# Main.net
KiCad netlist of a schematic drawn in Altium Designer
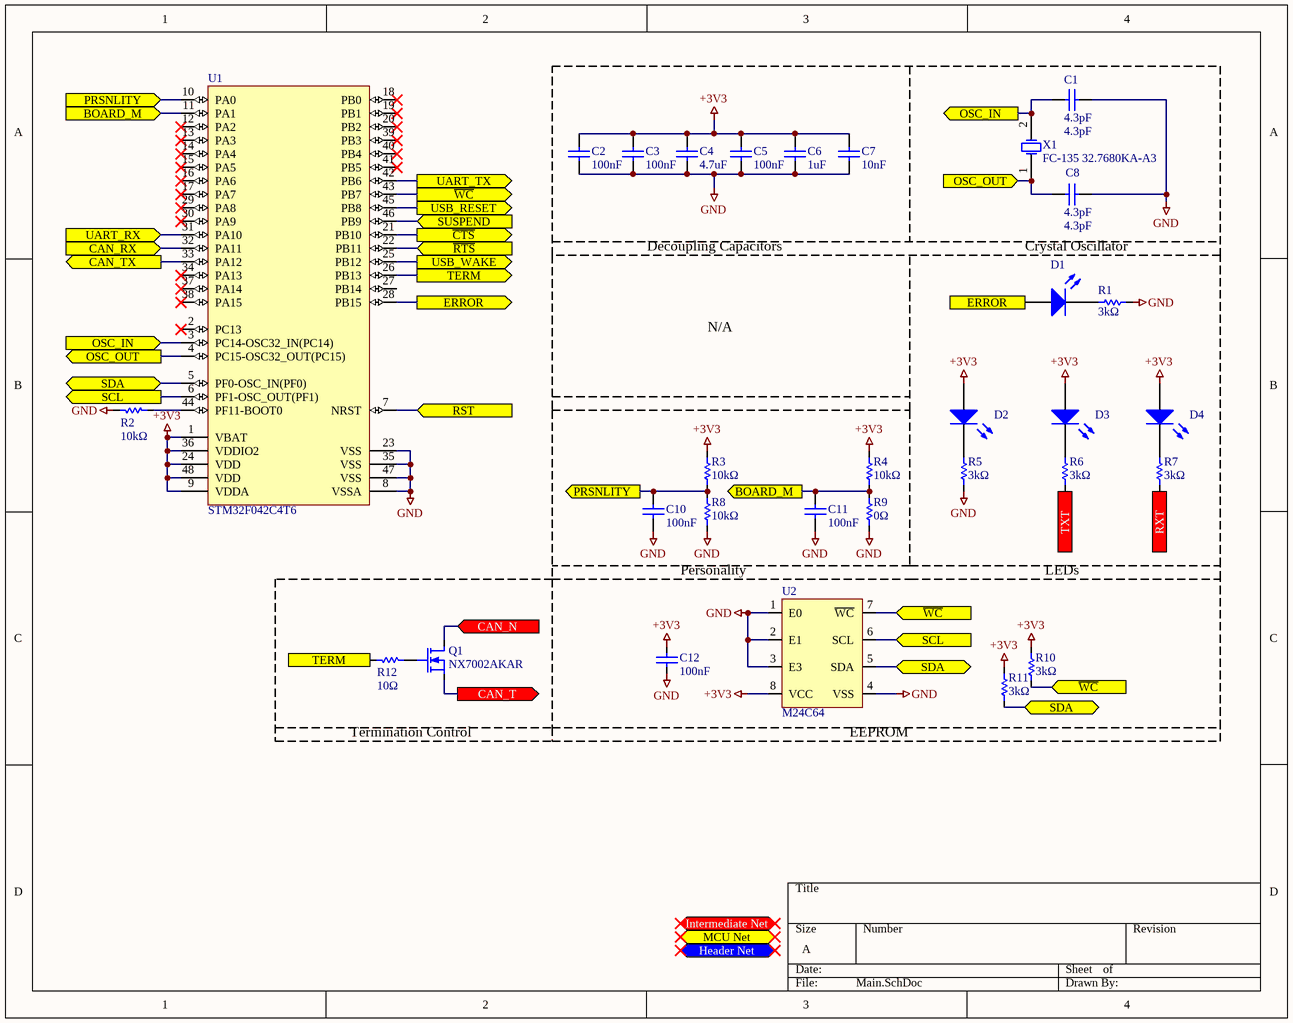
[diagram p0: Main.SchDoc]

(export (version "E")
  (design (tool "Eeschema 10.0.6"))
  (components
    (comp (ref "C1")
      (value "4.3pF")
      (footprint "1608[0603]")
      (description "Capacitor (Semiconductor SIM Model)")
      (fields (field (name "ALTIUM_VALUE") "4.3pF") (field (name "PUBLISHER") "Altium Limited"))
      (libsource (lib "Miscellaneous Devices") (part "Cap Semi"))
    )
    (comp (ref "C2")
      (value "100nF")
      (footprint "1608[0603]")
      (description "Capacitor (Semiconductor SIM Model)")
      (fields (field (name "PUBLISHER") "Altium Limited"))
      (libsource (lib "Miscellaneous Devices") (part "Cap Semi"))
    )
    (comp (ref "C3")
      (value "100nF")
      (footprint "1608[0603]")
      (description "Capacitor (Semiconductor SIM Model)")
      (fields (field (name "PUBLISHER") "Altium Limited"))
      (libsource (lib "Miscellaneous Devices") (part "Cap Semi"))
    )
    (comp (ref "C4")
      (value "4.7uF")
      (footprint "1608[0603]")
      (description "Capacitor (Semiconductor SIM Model)")
      (fields (field (name "PUBLISHER") "Altium Limited"))
      (libsource (lib "Miscellaneous Devices") (part "Cap Semi"))
    )
    (comp (ref "C5")
      (value "100nF")
      (footprint "1608[0603]")
      (description "Capacitor (Semiconductor SIM Model)")
      (fields (field (name "PUBLISHER") "Altium Limited"))
      (libsource (lib "Miscellaneous Devices") (part "Cap Semi"))
    )
    (comp (ref "C6")
      (value "1uF")
      (footprint "1608[0603]")
      (description "Capacitor (Semiconductor SIM Model)")
      (fields (field (name "PUBLISHER") "Altium Limited"))
      (libsource (lib "Miscellaneous Devices") (part "Cap Semi"))
    )
    (comp (ref "C7")
      (value "10nF")
      (footprint "1608[0603]")
      (description "Capacitor (Semiconductor SIM Model)")
      (fields (field (name "PUBLISHER") "Altium Limited"))
      (libsource (lib "Miscellaneous Devices") (part "Cap Semi"))
    )
    (comp (ref "C8")
      (value "4.3pF")
      (footprint "1608[0603]")
      (description "Capacitor (Semiconductor SIM Model)")
      (fields (field (name "ALTIUM_VALUE") "4.3pF") (field (name "PUBLISHER") "Altium Limited"))
      (libsource (lib "Miscellaneous Devices") (part "Cap Semi"))
    )
    (comp (ref "C10")
      (value "100nF")
      (footprint "1608[0603]")
      (description "Capacitor (Semiconductor SIM Model)")
      (fields (field (name "PUBLISHER") "Altium Limited"))
      (libsource (lib "Miscellaneous Devices") (part "Cap Semi"))
    )
    (comp (ref "C11")
      (value "100nF")
      (footprint "1608[0603]")
      (description "Capacitor (Semiconductor SIM Model)")
      (fields (field (name "PUBLISHER") "Altium Limited"))
      (libsource (lib "Miscellaneous Devices") (part "Cap Semi"))
    )
    (comp (ref "C12")
      (value "100nF")
      (footprint "1608[0603]")
      (description "Capacitor (Semiconductor SIM Model)")
      (fields (field (name "PUBLISHER") "Altium Limited"))
      (libsource (lib "") (part "Cap Semi_1"))
    )
    (comp (ref "D1")
      (value "POWER_ON")
      (footprint "1608[0603]")
      (description "Typical RED, GREEN, YELLOW, AMBER GaAs LED")
      (fields (field (name "PUBLISHER") "Altium Limited"))
      (libsource (lib "Miscellaneous Devices") (part "LED2"))
    )
    (comp (ref "D2")
      (value "POWER_ON")
      (footprint "1608[0603]")
      (description "Typical RED, GREEN, YELLOW, AMBER GaAs LED")
      (fields (field (name "PUBLISHER") "Altium Limited"))
      (libsource (lib "Miscellaneous Devices") (part "LED2"))
    )
    (comp (ref "D3")
      (value "POWER_ON")
      (footprint "1608[0603]")
      (description "Typical RED, GREEN, YELLOW, AMBER GaAs LED")
      (fields (field (name "PUBLISHER") "Altium Limited"))
      (libsource (lib "Miscellaneous Devices") (part "LED2"))
    )
    (comp (ref "D4")
      (value "POWER_ON")
      (footprint "1608[0603]")
      (description "Typical RED, GREEN, YELLOW, AMBER GaAs LED")
      (fields (field (name "PUBLISHER") "Altium Limited"))
      (libsource (lib "Miscellaneous Devices") (part "LED2"))
    )
    (comp (ref "Q1")
      (value "NX7002AKAR")
      (footprint "SOT23-6_L")
      (description "N-Channel MOSFET")
      (fields (field (name "PUBLISHER") "Altium Limited"))
      (libsource (lib "Miscellaneous Devices") (part "MOSFET-N"))
    )
    (comp (ref "R1")
      (value "3kΩ")
      (footprint "1608[0603]")
      (description "Resistor")
      (fields (field (name "Comment") "4.7k") (field (name "PUBLISHER") "Altium Limited"))
      (libsource (lib "Miscellaneous Devices") (part "Res1"))
    )
    (comp (ref "R2")
      (value "10kΩ")
      (footprint "1608[0603]")
      (description "Resistor")
      (fields (field (name "Comment") "10k") (field (name "PUBLISHER") "Altium Limited"))
      (libsource (lib "Miscellaneous Devices") (part "Res1"))
    )
    (comp (ref "R3")
      (value "10kΩ")
      (footprint "1608[0603]")
      (description "Resistor")
      (fields (field (name "Comment") "10k") (field (name "PUBLISHER") "Altium Limited"))
      (libsource (lib "Miscellaneous Devices") (part "Res1"))
    )
    (comp (ref "R4")
      (value "10kΩ")
      (footprint "1608[0603]")
      (description "Resistor")
      (fields (field (name "Comment") "10k") (field (name "PUBLISHER") "Altium Limited"))
      (libsource (lib "Miscellaneous Devices") (part "Res1"))
    )
    (comp (ref "R5")
      (value "3kΩ")
      (footprint "1608[0603]")
      (description "Resistor")
      (fields (field (name "Comment") "4.7k") (field (name "PUBLISHER") "Altium Limited"))
      (libsource (lib "Miscellaneous Devices") (part "Res1"))
    )
    (comp (ref "R6")
      (value "3kΩ")
      (footprint "1608[0603]")
      (description "Resistor")
      (fields (field (name "Comment") "4.7k") (field (name "PUBLISHER") "Altium Limited"))
      (libsource (lib "Miscellaneous Devices") (part "Res1"))
    )
    (comp (ref "R7")
      (value "3kΩ")
      (footprint "1608[0603]")
      (description "Resistor")
      (fields (field (name "Comment") "4.7k") (field (name "PUBLISHER") "Altium Limited"))
      (libsource (lib "Miscellaneous Devices") (part "Res1"))
    )
    (comp (ref "R8")
      (value "10kΩ")
      (footprint "1608[0603]")
      (description "Resistor")
      (fields (field (name "Comment") "10k") (field (name "PUBLISHER") "Altium Limited"))
      (libsource (lib "Miscellaneous Devices") (part "Res1"))
    )
    (comp (ref "R9")
      (value "0Ω")
      (footprint "1608[0603]")
      (description "Resistor")
      (fields (field (name "Comment") "0 ohm") (field (name "PUBLISHER") "Altium Limited"))
      (libsource (lib "Miscellaneous Devices") (part "Res1"))
    )
    (comp (ref "R10")
      (value "3kΩ")
      (footprint "1608[0603]")
      (description "Resistor")
      (fields (field (name "Comment") "3k") (field (name "PUBLISHER") "Altium Limited"))
      (libsource (lib "Miscellaneous Devices") (part "Res1"))
    )
    (comp (ref "R11")
      (value "3kΩ")
      (footprint "1608[0603]")
      (description "Resistor")
      (fields (field (name "Comment") "3k") (field (name "PUBLISHER") "Altium Limited"))
      (libsource (lib "Miscellaneous Devices") (part "Res1"))
    )
    (comp (ref "R12")
      (value "10Ω")
      (footprint "1608[0603]")
      (description "Resistor")
      (fields (field (name "Comment") "10k") (field (name "PUBLISHER") "Altium Limited"))
      (libsource (lib "Miscellaneous Devices") (part "Res1"))
    )
    (comp (ref "U1")
      (value "STM32F042C4T6")
      (footprint "STM-LQFP48_M")
      (fields (field (name "MANUFACTURER") "STMicroelectronics"))
      (libsource (lib "Altium Content Vault") (part "MC-ARM-STM32F042-LQFP48"))
    )
    (comp (ref "U2")
      (value "M24C64")
      (footprint "SO8_M")
      (description "EEPROM I2C 64k")
      (libsource (lib "BMS") (part "M24C64-RMN6P"))
    )
    (comp (ref "X1")
      (value "FC-135 32.7680KA-A3")
      (footprint "ESPO-FC-135-2_V")
      (description "Crystal, 32.768 KHz, 12.5 pF, -40 to 85 degC, 2-Pin SMD, RoHS, Tape and Reel")
      (fields (field (name "MANUFACTURER") "Epson") (field (name "TOLERANCE") "20PPM"))
      (libsource (lib "Altium Content Vault") (part "XTAL_1-2-2"))
    )
  )
  (nets
    (net (code "1") (name "+3V3") (class "Default")
      (node (ref "C12") (pin "1") (pinfunction "1_1") (pintype "passive"))
      (node (ref "C2") (pin "1") (pinfunction "1_1") (pintype "passive"))
      (node (ref "C3") (pin "1") (pinfunction "1_1") (pintype "passive"))
      (node (ref "C4") (pin "1") (pinfunction "1_1") (pintype "passive"))
      (node (ref "C5") (pin "1") (pinfunction "1_1") (pintype "passive"))
      (node (ref "C6") (pin "1") (pinfunction "1_1") (pintype "passive"))
      (node (ref "C7") (pin "1") (pinfunction "1_1") (pintype "passive"))
      (node (ref "D2") (pin "1") (pinfunction "A_1") (pintype "passive"))
      (node (ref "D3") (pin "1") (pinfunction "A_1") (pintype "passive"))
      (node (ref "D4") (pin "1") (pinfunction "A_1") (pintype "passive"))
      (node (ref "R10") (pin "1") (pinfunction "1_1") (pintype "passive"))
      (node (ref "R11") (pin "1") (pinfunction "1_1") (pintype "passive"))
      (node (ref "R3") (pin "2") (pinfunction "2_2") (pintype "passive"))
      (node (ref "R4") (pin "2") (pinfunction "2_2") (pintype "passive"))
      (node (ref "U1") (pin "1") (pinfunction "VBAT_1") (pintype "power_in"))
      (node (ref "U1") (pin "24") (pinfunction "VDD_24") (pintype "power_in"))
      (node (ref "U1") (pin "36") (pinfunction "VDDIO2_36") (pintype "power_in"))
      (node (ref "U1") (pin "48") (pinfunction "VDD_48") (pintype "power_in"))
      (node (ref "U1") (pin "9") (pinfunction "VDDA_9") (pintype "power_in"))
      (node (ref "U2") (pin "8") (pinfunction "VCC_8") (pintype "passive"))
    )
    (net (code "2") (name "/BOARD_M") (class "Default")
      (node (ref "C11") (pin "1") (pinfunction "1_1") (pintype "passive"))
      (node (ref "R4") (pin "1") (pinfunction "1_1") (pintype "passive"))
      (node (ref "R9") (pin "2") (pinfunction "2_2") (pintype "passive"))
      (node (ref "U1") (pin "11") (pinfunction "PA1_11") (pintype "bidirectional"))
    )
    (net (code "3") (name "/CAN_N") (class "Default")
      (node (ref "Q1") (pin "1") (pinfunction "D_1") (pintype "passive"))
    )
    (net (code "4") (name "/CAN_RX") (class "Default")
      (node (ref "U1") (pin "32") (pinfunction "PA11_32") (pintype "bidirectional"))
    )
    (net (code "5") (name "/CAN_T") (class "Default")
      (node (ref "Q1") (pin "3") (pinfunction "S_3") (pintype "passive"))
    )
    (net (code "6") (name "/CAN_TX") (class "Default")
      (node (ref "U1") (pin "33") (pinfunction "PA12_33") (pintype "bidirectional"))
    )
    (net (code "7") (name "/ERROR") (class "Default")
      (node (ref "D1") (pin "1") (pinfunction "A_1") (pintype "passive"))
      (node (ref "U1") (pin "28") (pinfunction "PB15_28") (pintype "bidirectional"))
    )
    (net (code "11") (name "/OSC_IN") (class "Default")
      (node (ref "C1") (pin "1") (pinfunction "1_1") (pintype "passive"))
      (node (ref "U1") (pin "3") (pinfunction "PC14-OSC32_IN(PC14)_3") (pintype "bidirectional"))
      (node (ref "X1") (pin "2") (pinfunction "X2_2") (pintype "passive"))
    )
    (net (code "12") (name "/OSC_OUT") (class "Default")
      (node (ref "C8") (pin "1") (pinfunction "1_1") (pintype "passive"))
      (node (ref "U1") (pin "4") (pinfunction "PC15-OSC32_OUT(PC15)_4") (pintype "bidirectional"))
      (node (ref "X1") (pin "1") (pinfunction "X1_1") (pintype "passive"))
    )
    (net (code "13") (name "/PRSNLITY") (class "Default")
      (node (ref "C10") (pin "1") (pinfunction "1_1") (pintype "passive"))
      (node (ref "R3") (pin "1") (pinfunction "1_1") (pintype "passive"))
      (node (ref "R8") (pin "2") (pinfunction "2_2") (pintype "passive"))
      (node (ref "U1") (pin "10") (pinfunction "PA0_10") (pintype "bidirectional"))
    )
    (net (code "14") (name "/RST") (class "Default")
      (node (ref "U1") (pin "7") (pinfunction "NRST_7") (pintype "bidirectional"))
    )
    (net (code "15") (name "/RXT") (class "Default")
      (node (ref "R7") (pin "2") (pinfunction "2_2") (pintype "passive"))
    )
    (net (code "16") (name "/SCL") (class "Default")
      (node (ref "U1") (pin "6") (pinfunction "PF1-OSC_OUT(PF1)_6") (pintype "bidirectional"))
      (node (ref "U2") (pin "6") (pinfunction "SCL_6") (pintype "passive"))
    )
    (net (code "17") (name "/SDA") (class "Default")
      (node (ref "R11") (pin "2") (pinfunction "2_2") (pintype "passive"))
      (node (ref "U1") (pin "5") (pinfunction "PF0-OSC_IN(PF0)_5") (pintype "bidirectional"))
      (node (ref "U2") (pin "5") (pinfunction "SDA_5") (pintype "passive"))
    )
    (net (code "18") (name "/SUSPEND") (class "Default")
      (node (ref "U1") (pin "46") (pinfunction "PB9_46") (pintype "bidirectional"))
    )
    (net (code "19") (name "/TERM") (class "Default")
      (node (ref "R12") (pin "2") (pinfunction "2_2") (pintype "passive"))
      (node (ref "U1") (pin "26") (pinfunction "PB13_26") (pintype "bidirectional"))
    )
    (net (code "20") (name "/TXT") (class "Default")
      (node (ref "R6") (pin "2") (pinfunction "2_2") (pintype "passive"))
    )
    (net (code "21") (name "/UART_RX") (class "Default")
      (node (ref "U1") (pin "31") (pinfunction "PA10_31") (pintype "bidirectional"))
    )
    (net (code "22") (name "/UART_TX") (class "Default")
      (node (ref "U1") (pin "42") (pinfunction "PB6_42") (pintype "bidirectional"))
    )
    (net (code "23") (name "/USB_RESET") (class "Default")
      (node (ref "U1") (pin "45") (pinfunction "PB8_45") (pintype "bidirectional"))
    )
    (net (code "24") (name "/USB_WAKE") (class "Default")
      (node (ref "U1") (pin "25") (pinfunction "PB12_25") (pintype "bidirectional"))
    )
    (net (code "25") (name "/~{CTS}") (class "Default")
      (node (ref "U1") (pin "21") (pinfunction "PB10_21") (pintype "bidirectional"))
    )
    (net (code "26") (name "/~{RTS}") (class "Default")
      (node (ref "U1") (pin "22") (pinfunction "PB11_22") (pintype "bidirectional"))
    )
    (net (code "27") (name "/~{WC}") (class "Default")
      (node (ref "R10") (pin "2") (pinfunction "2_2") (pintype "passive"))
      (node (ref "U1") (pin "43") (pinfunction "PB7_43") (pintype "bidirectional"))
      (node (ref "U2") (pin "7") (pinfunction "~{WC}_7") (pintype "passive"))
    )
    (net (code "28") (name "GND") (class "Default")
      (node (ref "C1") (pin "2") (pinfunction "2_2") (pintype "passive"))
      (node (ref "C10") (pin "2") (pinfunction "2_2") (pintype "passive"))
      (node (ref "C11") (pin "2") (pinfunction "2_2") (pintype "passive"))
      (node (ref "C12") (pin "2") (pinfunction "2_2") (pintype "passive"))
      (node (ref "C2") (pin "2") (pinfunction "2_2") (pintype "passive"))
      (node (ref "C3") (pin "2") (pinfunction "2_2") (pintype "passive"))
      (node (ref "C4") (pin "2") (pinfunction "2_2") (pintype "passive"))
      (node (ref "C5") (pin "2") (pinfunction "2_2") (pintype "passive"))
      (node (ref "C6") (pin "2") (pinfunction "2_2") (pintype "passive"))
      (node (ref "C7") (pin "2") (pinfunction "2_2") (pintype "passive"))
      (node (ref "C8") (pin "2") (pinfunction "2_2") (pintype "passive"))
      (node (ref "R1") (pin "2") (pinfunction "2_2") (pintype "passive"))
      (node (ref "R2") (pin "2") (pinfunction "2_2") (pintype "passive"))
      (node (ref "R5") (pin "2") (pinfunction "2_2") (pintype "passive"))
      (node (ref "R8") (pin "1") (pinfunction "1_1") (pintype "passive"))
      (node (ref "R9") (pin "1") (pinfunction "1_1") (pintype "passive"))
      (node (ref "U1") (pin "23") (pinfunction "VSS_23") (pintype "power_in"))
      (node (ref "U1") (pin "35") (pinfunction "VSS_35") (pintype "power_in"))
      (node (ref "U1") (pin "47") (pinfunction "VSS_47") (pintype "power_in"))
      (node (ref "U1") (pin "8") (pinfunction "VSSA_8") (pintype "power_in"))
      (node (ref "U2") (pin "1") (pinfunction "E0_1") (pintype "passive"))
      (node (ref "U2") (pin "2") (pinfunction "E1_2") (pintype "passive"))
      (node (ref "U2") (pin "3") (pinfunction "E3_3") (pintype "passive"))
      (node (ref "U2") (pin "4") (pinfunction "VSS_4") (pintype "passive"))
    )
    (net (code "29") (name "Net-(D1-K)") (class "Default")
      (node (ref "D1") (pin "2") (pinfunction "K_2") (pintype "passive"))
      (node (ref "R1") (pin "1") (pinfunction "1_1") (pintype "passive"))
    )
    (net (code "30") (name "Net-(D2-K)") (class "Default")
      (node (ref "D2") (pin "2") (pinfunction "K_2") (pintype "passive"))
      (node (ref "R5") (pin "1") (pinfunction "1_1") (pintype "passive"))
    )
    (net (code "31") (name "Net-(D3-K)") (class "Default")
      (node (ref "D3") (pin "2") (pinfunction "K_2") (pintype "passive"))
      (node (ref "R6") (pin "1") (pinfunction "1_1") (pintype "passive"))
    )
    (net (code "32") (name "Net-(D4-K)") (class "Default")
      (node (ref "D4") (pin "2") (pinfunction "K_2") (pintype "passive"))
      (node (ref "R7") (pin "1") (pinfunction "1_1") (pintype "passive"))
    )
    (net (code "33") (name "Net-(Q1-G)") (class "Default")
      (node (ref "Q1") (pin "2") (pinfunction "G_2") (pintype "passive"))
      (node (ref "R12") (pin "1") (pinfunction "1_1") (pintype "passive"))
    )
    (net (code "34") (name "Net-(U1-PF11-BOOT0)") (class "Default")
      (node (ref "R2") (pin "1") (pinfunction "1_1") (pintype "passive"))
      (node (ref "U1") (pin "44") (pinfunction "PF11-BOOT0_44") (pintype "bidirectional"))
    )
    (net (code "35") (name "unconnected-(U1-PA2-Pad12)") (class "Default")
      (node (ref "U1") (pin "12") (pinfunction "PA2_12") (pintype "bidirectional+no_connect"))
    )
    (net (code "36") (name "unconnected-(U1-PA3-Pad13)") (class "Default")
      (node (ref "U1") (pin "13") (pinfunction "PA3_13") (pintype "bidirectional+no_connect"))
    )
    (net (code "37") (name "unconnected-(U1-PA4-Pad14)") (class "Default")
      (node (ref "U1") (pin "14") (pinfunction "PA4_14") (pintype "bidirectional+no_connect"))
    )
    (net (code "38") (name "unconnected-(U1-PA5-Pad15)") (class "Default")
      (node (ref "U1") (pin "15") (pinfunction "PA5_15") (pintype "bidirectional+no_connect"))
    )
    (net (code "39") (name "unconnected-(U1-PA6-Pad16)") (class "Default")
      (node (ref "U1") (pin "16") (pinfunction "PA6_16") (pintype "bidirectional+no_connect"))
    )
    (net (code "40") (name "unconnected-(U1-PA7-Pad17)") (class "Default")
      (node (ref "U1") (pin "17") (pinfunction "PA7_17") (pintype "bidirectional+no_connect"))
    )
    (net (code "41") (name "unconnected-(U1-PA8-Pad29)") (class "Default")
      (node (ref "U1") (pin "29") (pinfunction "PA8_29") (pintype "bidirectional+no_connect"))
    )
    (net (code "42") (name "unconnected-(U1-PA9-Pad30)") (class "Default")
      (node (ref "U1") (pin "30") (pinfunction "PA9_30") (pintype "bidirectional+no_connect"))
    )
    (net (code "43") (name "unconnected-(U1-PA13-Pad34)") (class "Default")
      (node (ref "U1") (pin "34") (pinfunction "PA13_34") (pintype "bidirectional+no_connect"))
    )
    (net (code "44") (name "unconnected-(U1-PA14-Pad37)") (class "Default")
      (node (ref "U1") (pin "37") (pinfunction "PA14_37") (pintype "bidirectional+no_connect"))
    )
    (net (code "45") (name "unconnected-(U1-PA15-Pad38)") (class "Default")
      (node (ref "U1") (pin "38") (pinfunction "PA15_38") (pintype "bidirectional+no_connect"))
    )
    (net (code "46") (name "unconnected-(U1-PB0-Pad18)") (class "Default")
      (node (ref "U1") (pin "18") (pinfunction "PB0_18") (pintype "bidirectional+no_connect"))
    )
    (net (code "47") (name "unconnected-(U1-PB1-Pad19)") (class "Default")
      (node (ref "U1") (pin "19") (pinfunction "PB1_19") (pintype "bidirectional+no_connect"))
    )
    (net (code "48") (name "unconnected-(U1-PB2-Pad20)") (class "Default")
      (node (ref "U1") (pin "20") (pinfunction "PB2_20") (pintype "bidirectional+no_connect"))
    )
    (net (code "49") (name "unconnected-(U1-PB3-Pad39)") (class "Default")
      (node (ref "U1") (pin "39") (pinfunction "PB3_39") (pintype "bidirectional+no_connect"))
    )
    (net (code "50") (name "unconnected-(U1-PB4-Pad40)") (class "Default")
      (node (ref "U1") (pin "40") (pinfunction "PB4_40") (pintype "bidirectional+no_connect"))
    )
    (net (code "51") (name "unconnected-(U1-PB5-Pad41)") (class "Default")
      (node (ref "U1") (pin "41") (pinfunction "PB5_41") (pintype "bidirectional+no_connect"))
    )
    (net (code "52") (name "unconnected-(U1-PB14-Pad27)") (class "Default")
      (node (ref "U1") (pin "27") (pinfunction "PB14_27") (pintype "bidirectional"))
    )
    (net (code "53") (name "unconnected-(U1-PC13-Pad2)") (class "Default")
      (node (ref "U1") (pin "2") (pinfunction "PC13_2") (pintype "bidirectional+no_connect"))
    )
  )
)
